# Power.net
KiCad netlist of a schematic drawn in Altium Designer
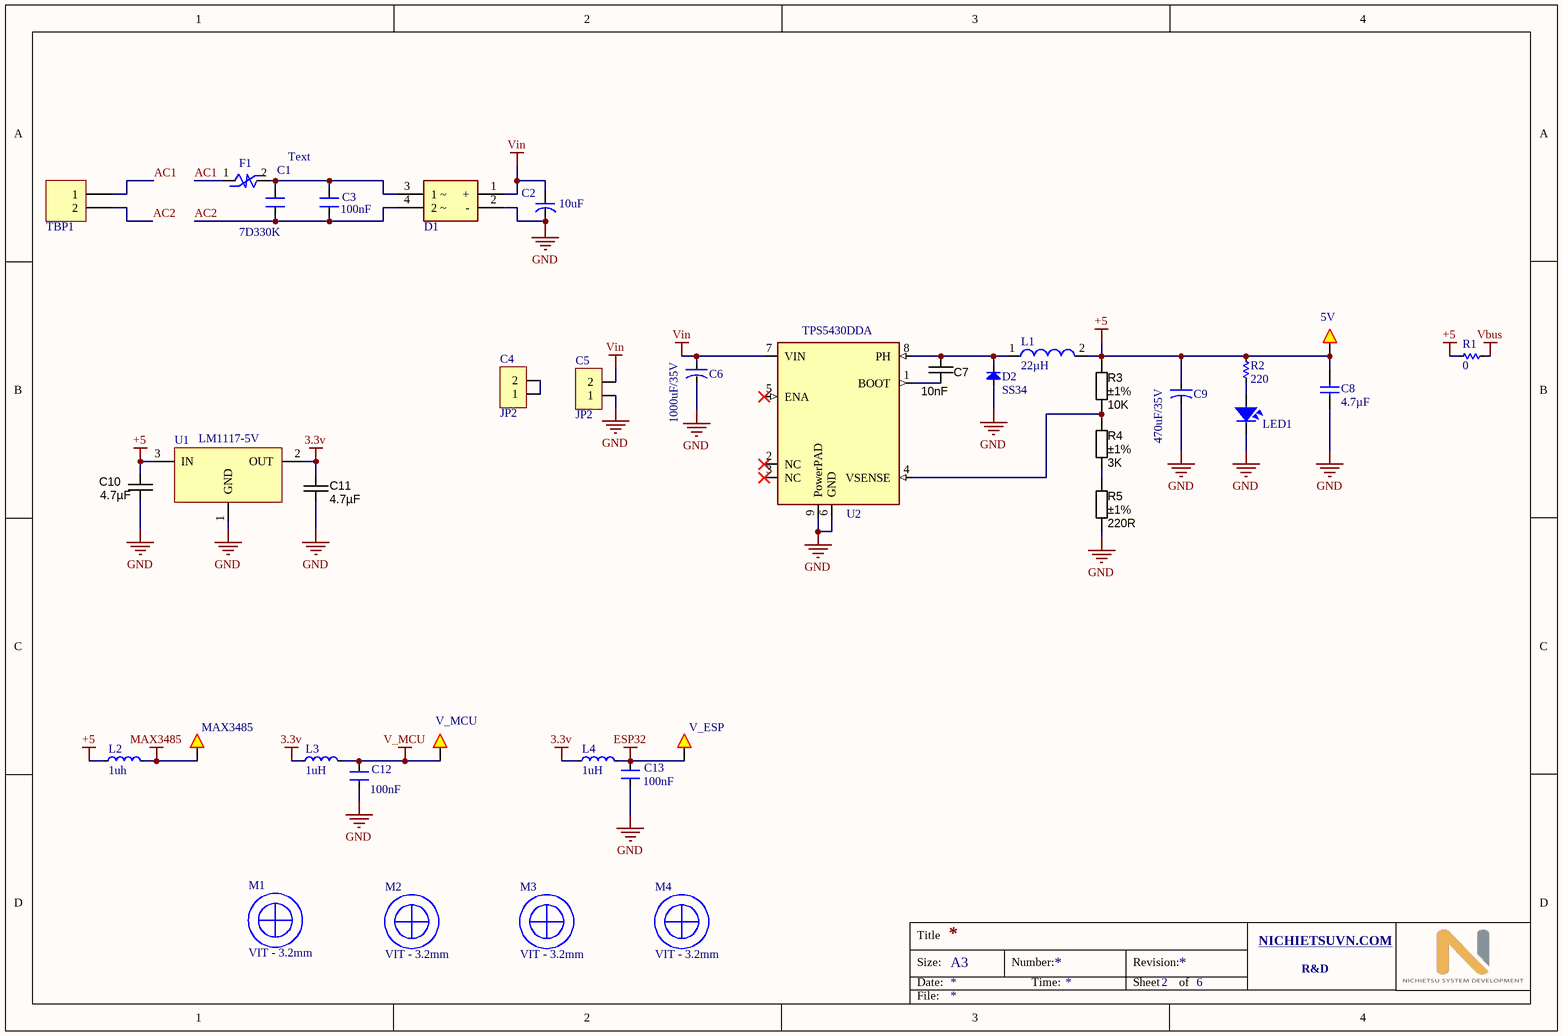
[diagram p0: Power.SchDoc]

(export (version "E")
  (design (tool "Eeschema 10.0.6"))
  (components
    (comp (ref "C1") (value "7D330K") (footprint "CN2-G") (libsource (lib "thu vien 3d") (part "CN")))
    (comp (ref "C2")
      (value "10uF")
      (footprint "CN-SMD-0805")
      (description "capacitor tantalum, pol")
      (libsource (lib "Nichietsuvn") (part "CAP_1"))
    )
    (comp (ref "C3") (value "100nF") (footprint "CN1") (libsource (lib "thu vien 3d") (part "CN")))
    (comp (ref "C4")
      (value "JP2")
      (footprint "JP2-C1T")
      (description "WR-PHD 2.54 mm Angled Socket Header")
      (fields
        (field (name "MANUFACTURER") "Würth Elektronik eiSos GmbH")
        (field (name "PARTNO") "613002143121")
        (field (name "CREATED BY") "Karrer Zheng")
      )
      (libsource (lib "thu vien 3d") (part "JP2"))
    )
    (comp (ref "C5")
      (value "JP2")
      (footprint "JP2-C1T")
      (description "WR-PHD 2.54 mm Angled Socket Header")
      (fields
        (field (name "MANUFACTURER") "Würth Elektronik eiSos GmbH")
        (field (name "PARTNO") "613002143121")
        (field (name "CREATED BY") "Karrer Zheng")
      )
      (libsource (lib "thu vien 3d") (part "JP2"))
    )
    (comp (ref "C6")
      (value "1000uF/35V")
      (footprint "CA-ALU-5W")
      (description "Capacitor (Semiconductor SIM Model)")
      (fields (field (name "PUBLISHER") "Altium Limited"))
      (libsource (lib "thu vien 3d") (part "CN-ALU-DIP"))
    )
    (comp (ref "C7")
      (value "10nF")
      (footprint "CAPC1608X90N")
      (description "10000pF ±10% 50V Ceramic Capacitor X7R 0603 (1608 Metric)")
      (fields (field (name "TOLERANCE") "±10%"))
      (libsource (lib "SangMV") (part "CAPC_10000pF_0603_50V_10%"))
    )
    (comp (ref "C8")
      (value "4.7µF")
      (footprint "CAPC1608X06L")
      (description "Capacitor, X5R, ±10%")
      (fields (field (name "PART NUMBER") "C0603-4µ7") (field (name "PUBLISHER") "Nordic Semiconductor"))
      (libsource (lib "All Library") (part "CAP_0603"))
    )
    (comp (ref "C9")
      (value "470uF/35V")
      (footprint "CA-ALU-5W")
      (description "Capacitor (Semiconductor SIM Model)")
      (fields (field (name "PUBLISHER") "Altium Limited"))
      (libsource (lib "thu vien 3d") (part "CN-ALU-DIP"))
    )
    (comp (ref "C10")
      (value "4.7µF")
      (footprint "CAPC2012X135N")
      (description "4.7µF ±10% 50V Ceramic Capacitor X7R 0805 (2012 Metric)")
      (fields
        (field (name "TOLERANCE") "±10%")
        (field (name "MANUFACTURER PART NUMBER") "CGA4J1X7R1H475K125AE")
      )
      (libsource (lib "All Library") (part "CAPC_4.7uF_0805_X7R_50V_10%"))
    )
    (comp (ref "C11")
      (value "4.7µF")
      (footprint "CAPC2012X135N")
      (description "4.7µF ±10% 50V Ceramic Capacitor X7R 0805 (2012 Metric)")
      (fields
        (field (name "TOLERANCE") "±10%")
        (field (name "MANUFACTURER PART NUMBER") "CGA4J1X7R1H475K125AE")
      )
      (libsource (lib "All Library") (part "CAPC_4.7uF_0805_X7R_50V_10%"))
    )
    (comp (ref "C12") (value "100nF") (footprint "CN-SMD-0603") (libsource (lib "thu vien 3d") (part "CN")))
    (comp (ref "C13") (value "100nF") (footprint "CN-SMD-0805") (libsource (lib "thu vien 3d") (part "CN")))
    (comp (ref "Check1")
      (value "5V")
      (footprint "SMD-2")
      (description "WR-PHD 2.54 mm Angled Socket Header")
      (fields
        (field (name "MANUFACTURER") "Würth Elektronik eiSos GmbH")
        (field (name "PARTNO") "613002143121")
        (field (name "CREATED BY") "Karrer Zheng")
      )
      (libsource (lib "Nichietsuvn") (part "Test"))
    )
    (comp (ref "D1") (value "MB6S") (footprint "MB6") (libsource (lib "Nichietsuvn") (part "MB6S")))
    (comp (ref "D2")
      (value "SS34")
      (footprint "DIO-SMD-106")
      (description "Default Diode")
      (fields (field (name "PUBLISHER") "Altium Limited"))
      (libsource (lib "thu vien 3d") (part "Diode SMD"))
    )
    (comp (ref "F1") (value "RUEF185") (footprint "RES-1WD") (libsource (lib "Nichietsuvn") (part "RUEF185")))
    (comp (ref "L1")
      (value "22µH")
      (footprint "IND_COIL_8D43")
      (description "22µH Shielded Wirewound Inductor 950mA 380mOhm Max Nonstandard")
      (libsource (lib "SangMV") (part "INDC_SMD_22uH_8D43"))
    )
    (comp (ref "L2")
      (value "1uh")
      (footprint "INDC1608X06L")
      (description "Chip inductor, IDC,min = 50 mA, ±20%")
      (fields (field (name "PART NUMBER") "L0603-10µ") (field (name "PUBLISHER") "Nordic Semiconductor"))
      (libsource (lib "All Library") (part "IND_0603"))
    )
    (comp (ref "L3")
      (value "1uH")
      (footprint "INDC1608X06L")
      (description "Chip inductor, IDC,min = 50 mA, ±20%")
      (fields (field (name "PART NUMBER") "L0603-10µ") (field (name "PUBLISHER") "Nordic Semiconductor"))
      (libsource (lib "All Library") (part "IND_0603"))
    )
    (comp (ref "L4")
      (value "1uH")
      (footprint "INDC1608X06L")
      (description "Chip inductor, IDC,min = 50 mA, ±20%")
      (fields (field (name "PART NUMBER") "L0603-10µ") (field (name "PUBLISHER") "Nordic Semiconductor"))
      (libsource (lib "All Library") (part "IND_0603"))
    )
    (comp (ref "LED1")
      (value "LED")
      (footprint "LED-0805-Blue")
      (libsource (lib "thu vien 3d") (part "LED SMD"))
    )
    (comp (ref "M1")
      (value "VIT - 3.2mm")
      (footprint "VIT - 3.2MM_2")
      (libsource (lib "Nichietsuvn") (part "VIT - 3.2mm"))
    )
    (comp (ref "M2")
      (value "VIT - 3.2mm")
      (footprint "VIT - 3.2MM_2")
      (libsource (lib "Nichietsuvn") (part "VIT - 3.2mm"))
    )
    (comp (ref "M3")
      (value "VIT - 3.2mm")
      (footprint "VIT - 3.2MM_2")
      (libsource (lib "Nichietsuvn") (part "VIT - 3.2mm"))
    )
    (comp (ref "M4")
      (value "VIT - 3.2mm")
      (footprint "VIT - 3.2MM_2")
      (libsource (lib "Nichietsuvn") (part "VIT - 3.2mm"))
    )
    (comp (ref "R1")
      (value "0")
      (footprint "RES-SMD-0603")
      (description "Resistor")
      (fields
        (field (name "MANUFACTURER") "Generic Components")
        (field (name "PUBLISHER") "Altium Hobart Technology Centre")
      )
      (libsource (lib "thu vien 3d") (part "Res-SMD"))
    )
    (comp (ref "R2")
      (value "220")
      (footprint "RES-SMD-0603")
      (description "Resistor")
      (fields
        (field (name "MANUFACTURER") "Generic Components")
        (field (name "PUBLISHER") "Altium Hobart Technology Centre")
      )
      (libsource (lib "thu vien 3d") (part "Res-SMD"))
    )
    (comp (ref "R3")
      (value "10K")
      (footprint "RESC1608X55N")
      (fields
        (field (name "MANUFACTURER") "Stackpole Electronics Inc")
        (field (name "MANUFACTURER PART NUMBER") "RMCF0603FT10K0")
        (field (name "TOLERANCE") "±1%")
        (field (name "Comment") "10K_0603_1%")
      )
      (libsource (lib "SangMV") (part "RES_10K_0603_1%"))
    )
    (comp (ref "R4")
      (value "3K")
      (footprint "RESC1608X55N")
      (description "3 kOhms ±1% 0.1W, 1/10W Chip Resistor 0603 (1608 Metric) Automotive AEC-Q200 Thick Film")
      (fields
        (field (name "MANUFACTURER") "Stackpole Electronics Inc")
        (field (name "MANUFACTURER PART NUMBER") "RMCF0603FT3K00")
        (field (name "TOLERANCE") "±1%")
      )
      (libsource (lib "SangMV") (part "RES_3K_0603_1%"))
    )
    (comp (ref "R5")
      (value "220R")
      (footprint "RESC1608X55N")
      (description "220 Ohms ±1% 0.1W, 1/10W Chip Resistor 0603 (1608 Metric) Automotive AEC-Q200 Thick Film")
      (fields
        (field (name "MANUFACTURER") "Stackpole Electronics Inc")
        (field (name "MANUFACTURER PART NUMBER") "RMCF0603FT220R")
        (field (name "TOLERANCE") "±1%")
      )
      (libsource (lib "SangMV") (part "RES_220R_0603_1%"))
    )
    (comp (ref "TBP1")
      (value "WE-Terminal Blocks Plugable Type 691322310002")
      (footprint "Terminal_Blocks_Pluggable_Socket__Right_Angle__3.81_mm_Pitch__2_Position")
      (description "WR-TBL Terminal block - serie 322 - 3.81 mm")
      (libsource (lib "All Library") (part "Terminal_Blocks_Pluggable_Socket__Right_Angle__3.81_mm_Pitch__2_Position"))
    )
    (comp (ref "U1")
      (value "LM1117-5V")
      (footprint "SOT223")
      (description "800mA Low-Dropout Linear Regulator")
      (fields (field (name "CREATOR") "Nguyen Ba Bien"))
      (libsource (lib "thu vien 3d") (part "LM1117"))
    )
    (comp (ref "U2")
      (value "TPS5430DDA")
      (footprint "TPS5430")
      (libsource (lib "Nichietsuvn") (part "TPS5430DDA"))
    )
    (comp (ref "V1")
      (value "MAX3485")
      (footprint "SMD_1")
      (description "WR-PHD 2.54 mm Angled Socket Header")
      (fields
        (field (name "MANUFACTURER") "Würth Elektronik eiSos GmbH")
        (field (name "PARTNO") "613002143121")
        (field (name "CREATED BY") "Karrer Zheng")
      )
      (libsource (lib "Nichietsuvn") (part "Test"))
    )
    (comp (ref "V2")
      (value "V_MCU")
      (footprint "SMD_1")
      (description "WR-PHD 2.54 mm Angled Socket Header")
      (fields
        (field (name "MANUFACTURER") "Würth Elektronik eiSos GmbH")
        (field (name "PARTNO") "613002143121")
        (field (name "CREATED BY") "Karrer Zheng")
      )
      (libsource (lib "Nichietsuvn") (part "Test"))
    )
    (comp (ref "V3")
      (value "V_ESP")
      (footprint "SMD_1")
      (description "WR-PHD 2.54 mm Angled Socket Header")
      (fields
        (field (name "MANUFACTURER") "Würth Elektronik eiSos GmbH")
        (field (name "PARTNO") "613002143121")
        (field (name "CREATED BY") "Karrer Zheng")
      )
      (libsource (lib "Nichietsuvn") (part "Test"))
    )
  )
  (nets
    (net (code "1") (name "+5") (class "Default")
      (node (ref "C10") (pin "2") (pintype "passive"))
      (node (ref "C8") (pin "2") (pinfunction "2_2") (pintype "passive"))
      (node (ref "C9") (pin "1") (pinfunction "1_1") (pintype "passive"))
      (node (ref "Check1") (pin "1") (pinfunction "1_1") (pintype "passive"))
      (node (ref "L1") (pin "2") (pinfunction "2_2") (pintype "passive"))
      (node (ref "L2") (pin "1") (pinfunction "1_1") (pintype "passive"))
      (node (ref "R1") (pin "1") (pinfunction "1_1") (pintype "passive"))
      (node (ref "R2") (pin "1") (pinfunction "1_1") (pintype "passive"))
      (node (ref "R3") (pin "2") (pinfunction "2_2") (pintype "passive"))
      (node (ref "U1") (pin "3") (pinfunction "IN_3") (pintype "passive"))
    )
    (net (code "2") (name "/AC1") (class "Default")
      (node (ref "F1") (pin "1") (pinfunction "1_1") (pintype "passive"))
      (node (ref "TBP1") (pin "1") (pinfunction "1_1") (pintype "passive"))
    )
    (net (code "3") (name "/AC2") (class "Default")
      (node (ref "C1") (pin "1") (pinfunction "1_1") (pintype "passive"))
      (node (ref "C3") (pin "2") (pinfunction "2_2") (pintype "passive"))
      (node (ref "D1") (pin "4") (pinfunction "2_~_4") (pintype "passive"))
      (node (ref "TBP1") (pin "2") (pinfunction "2_2") (pintype "passive"))
    )
    (net (code "4") (name "3.3v") (class "Default")
      (node (ref "C11") (pin "2") (pintype "passive"))
      (node (ref "L3") (pin "1") (pinfunction "1_1") (pintype "passive"))
      (node (ref "L4") (pin "1") (pinfunction "1_1") (pintype "passive"))
      (node (ref "U1") (pin "2") (pinfunction "OUT_2") (pintype "passive"))
    )
    (net (code "5") (name "ESP32") (class "Default")
      (node (ref "C13") (pin "1") (pinfunction "1_1") (pintype "passive"))
      (node (ref "L4") (pin "2") (pinfunction "2_2") (pintype "passive"))
      (node (ref "V3") (pin "1") (pinfunction "1_1") (pintype "passive"))
    )
    (net (code "6") (name "GND") (class "Default")
      (node (ref "C10") (pin "1") (pintype "passive"))
      (node (ref "C11") (pin "1") (pintype "passive"))
      (node (ref "C12") (pin "1") (pinfunction "1_1") (pintype "passive"))
      (node (ref "C13") (pin "2") (pinfunction "2_2") (pintype "passive"))
      (node (ref "C2") (pin "2") (pinfunction "2_2") (pintype "passive"))
      (node (ref "C5") (pin "1") (pinfunction "1_1") (pintype "passive"))
      (node (ref "C6") (pin "2") (pinfunction "2_2") (pintype "passive"))
      (node (ref "C8") (pin "1") (pinfunction "1_1") (pintype "passive"))
      (node (ref "C9") (pin "2") (pinfunction "2_2") (pintype "passive"))
      (node (ref "D1") (pin "2") (pinfunction "-_2") (pintype "passive"))
      (node (ref "D2") (pin "1") (pinfunction "A_1") (pintype "passive"))
      (node (ref "LED1") (pin "2") (pinfunction "2_2") (pintype "passive"))
      (node (ref "R5") (pin "1") (pinfunction "1_1") (pintype "passive"))
      (node (ref "U1") (pin "1") (pinfunction "GND_1") (pintype "passive"))
      (node (ref "U2") (pin "6") (pinfunction "GND_6") (pintype "power_in"))
      (node (ref "U2") (pin "9") (pinfunction "PowerPAD_9") (pintype "power_in"))
    )
    (net (code "7") (name "MAX3485") (class "Default")
      (node (ref "L2") (pin "2") (pinfunction "2_2") (pintype "passive"))
      (node (ref "V1") (pin "1") (pinfunction "1_1") (pintype "passive"))
    )
    (net (code "8") (name "Net-(C4-Pad1)") (class "Default")
      (node (ref "C4") (pin "1") (pinfunction "1_1") (pintype "passive"))
      (node (ref "C4") (pin "2") (pinfunction "2_2") (pintype "passive"))
    )
    (net (code "9") (name "Net-(D1-1_~)") (class "Default")
      (node (ref "C1") (pin "2") (pinfunction "2_2") (pintype "passive"))
      (node (ref "C3") (pin "1") (pinfunction "1_1") (pintype "passive"))
      (node (ref "D1") (pin "3") (pinfunction "1_~_3") (pintype "passive"))
      (node (ref "F1") (pin "2") (pinfunction "2_2") (pintype "passive"))
    )
    (net (code "10") (name "Net-(D2-K)") (class "Default")
      (node (ref "C7") (pin "2") (pintype "passive"))
      (node (ref "D2") (pin "2") (pinfunction "K_2") (pintype "passive"))
      (node (ref "L1") (pin "1") (pinfunction "1_1") (pintype "passive"))
      (node (ref "U2") (pin "8") (pinfunction "PH_8") (pintype "input"))
    )
    (net (code "11") (name "Net-(LED1-Pad1)") (class "Default")
      (node (ref "LED1") (pin "1") (pinfunction "1_1") (pintype "passive"))
      (node (ref "R2") (pin "2") (pinfunction "2_2") (pintype "passive"))
    )
    (net (code "12") (name "Net-(R4-Pad1)") (class "Default")
      (node (ref "R4") (pin "1") (pinfunction "1_1") (pintype "passive"))
      (node (ref "R5") (pin "2") (pinfunction "2_2") (pintype "passive"))
    )
    (net (code "13") (name "Net-(U2-BOOT)") (class "Default")
      (node (ref "C7") (pin "1") (pintype "passive"))
      (node (ref "U2") (pin "1") (pinfunction "BOOT_1") (pintype "output"))
    )
    (net (code "14") (name "Net-(U2-VSENSE)") (class "Default")
      (node (ref "R3") (pin "1") (pinfunction "1_1") (pintype "passive"))
      (node (ref "R4") (pin "2") (pinfunction "2_2") (pintype "passive"))
      (node (ref "U2") (pin "4") (pinfunction "VSENSE_4") (pintype "input"))
    )
    (net (code "15") (name "V_MCU") (class "Default")
      (node (ref "C12") (pin "2") (pinfunction "2_2") (pintype "passive"))
      (node (ref "L3") (pin "2") (pinfunction "2_2") (pintype "passive"))
      (node (ref "V2") (pin "1") (pinfunction "1_1") (pintype "passive"))
    )
    (net (code "16") (name "Vbus") (class "Default")
      (node (ref "R1") (pin "2") (pinfunction "2_2") (pintype "passive"))
    )
    (net (code "17") (name "Vin") (class "Default")
      (node (ref "C2") (pin "1") (pinfunction "1_1") (pintype "passive"))
      (node (ref "C5") (pin "2") (pinfunction "2_2") (pintype "passive"))
      (node (ref "C6") (pin "1") (pinfunction "1_1") (pintype "passive"))
      (node (ref "D1") (pin "1") (pinfunction "+_1") (pintype "passive"))
      (node (ref "U2") (pin "7") (pinfunction "VIN_7") (pintype "power_in"))
    )
    (net (code "18") (name "unconnected-(U2-ENA-Pad5)") (class "Default")
      (node (ref "U2") (pin "5") (pinfunction "ENA_5") (pintype "input+no_connect"))
    )
    (net (code "19") (name "unconnected-(U2-NC-Pad2)") (class "Default")
      (node (ref "U2") (pin "2") (pinfunction "NC_2") (pintype "passive+no_connect"))
    )
    (net (code "20") (name "unconnected-(U2-NC-Pad3)") (class "Default")
      (node (ref "U2") (pin "3") (pinfunction "NC_3") (pintype "passive+no_connect"))
    )
  )
)
